# miniarduinoisp.net
KiCad netlist of a schematic drawn in EAGLE
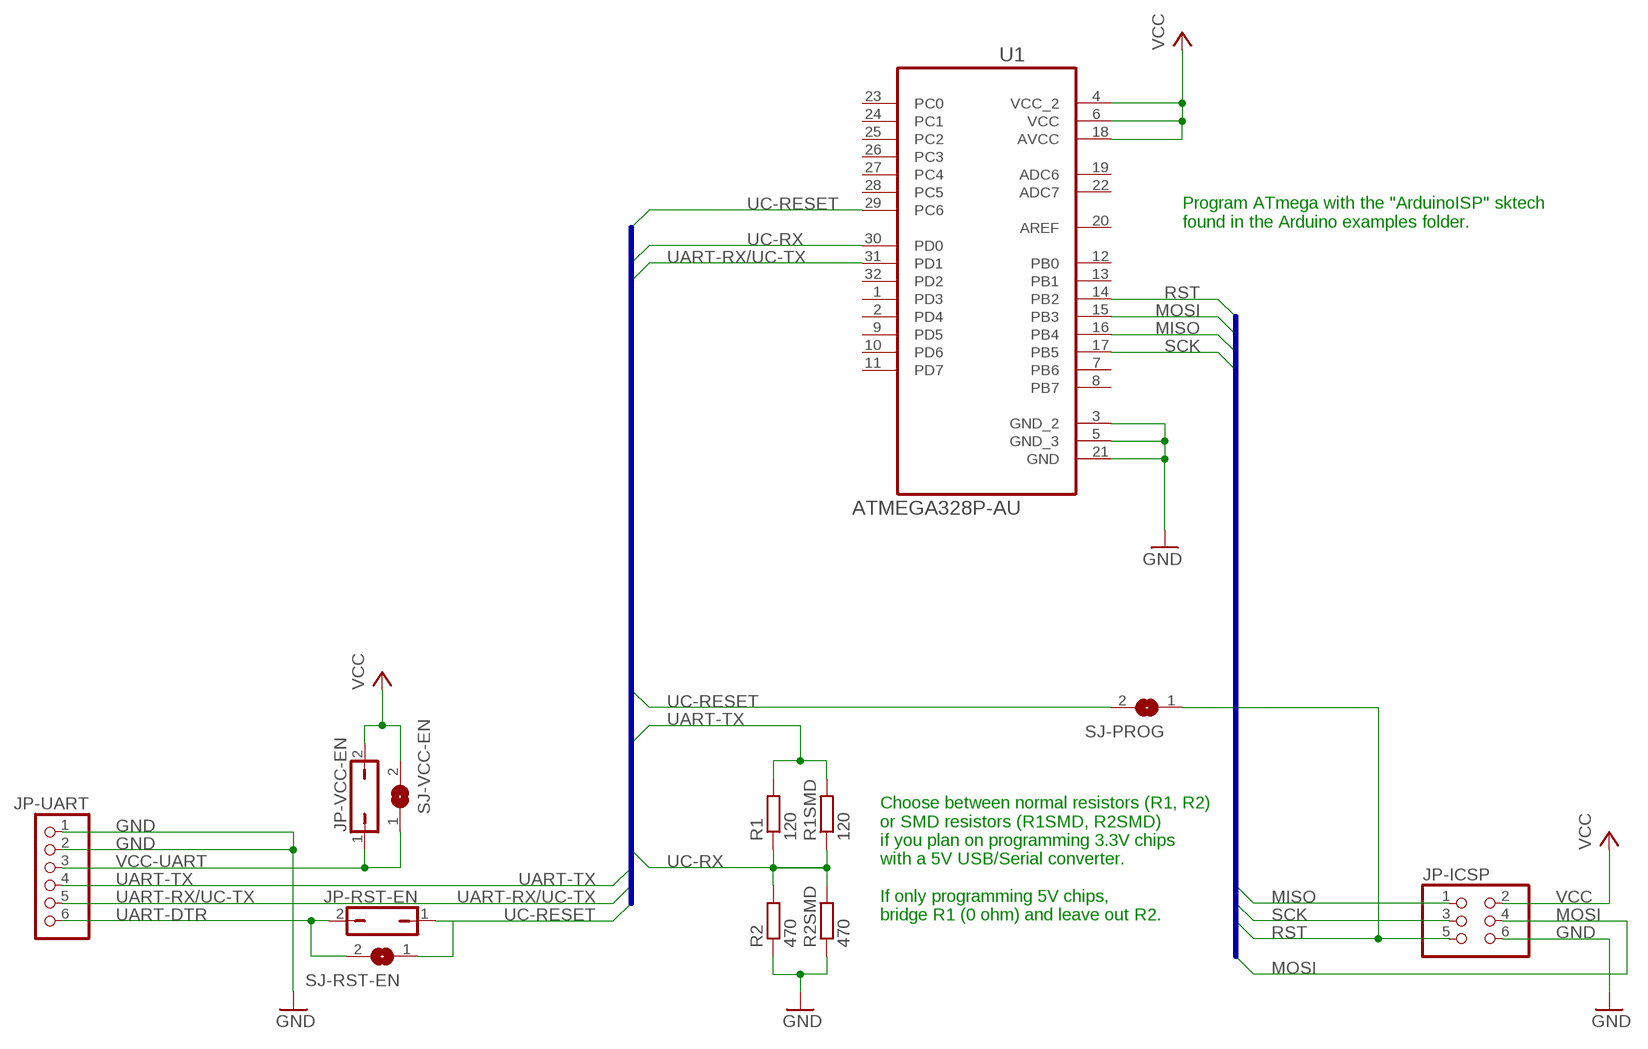
[diagram p0: schematic, sheet 1]

(export (version "E")
  (design (tool "Eeschema 10.0.6"))
  (components
    (comp (ref "JP-ICSP")
      (value "PINHD-2X3")
      (footprint "eagle-import:2X03")
      (libsource (lib "eagle-import") (part "PINHD-2X3"))
    )
    (comp (ref "JP-RST-EN")
      (value "JP1Q")
      (footprint "eagle-import:JP1")
      (libsource (lib "eagle-import") (part "JP1Q"))
    )
    (comp (ref "JP-UART")
      (value "PINHD-1X6/90")
      (footprint "eagle-import:1X06_90")
      (libsource (lib "eagle-import") (part "PINHD-1X6/90"))
    )
    (comp (ref "JP-VCC-EN")
      (value "JP1Q")
      (footprint "eagle-import:JP1")
      (libsource (lib "eagle-import") (part "JP1Q"))
    )
    (comp (ref "R1")
      (value "120")
      (footprint "eagle-import:0204_7")
      (libsource (lib "eagle-import") (part "R-EU_0204/7"))
    )
    (comp (ref "R1SMD")
      (value "120")
      (footprint "eagle-import:R0603")
      (libsource (lib "eagle-import") (part "R-EU_R0603"))
    )
    (comp (ref "R2")
      (value "470")
      (footprint "eagle-import:0204_7")
      (libsource (lib "eagle-import") (part "R-EU_0204/7"))
    )
    (comp (ref "R2SMD")
      (value "470")
      (footprint "eagle-import:R0603")
      (libsource (lib "eagle-import") (part "R-EU_R0603"))
    )
    (comp (ref "SJ-PROG")
      (value "SJ")
      (footprint "eagle-import:SJ")
      (libsource (lib "eagle-import") (part "SJ"))
    )
    (comp (ref "SJ-RST-EN")
      (value "SJ")
      (footprint "eagle-import:SJ")
      (libsource (lib "eagle-import") (part "SJ"))
    )
    (comp (ref "SJ-VCC-EN")
      (value "SJ")
      (footprint "eagle-import:SJ")
      (libsource (lib "eagle-import") (part "SJ"))
    )
    (comp (ref "U1")
      (value "ATMEGA328P-AU")
      (footprint "eagle-import:QFP80P900X900X120-32N")
      (libsource (lib "eagle-import") (part "ATMEGA328P-AU"))
    )
  )
  (nets
    (net (code "1") (name "/MISO") (class "Default")
      (node (ref "JP-ICSP") (pin "1") (pinfunction "1_1") (pintype "passive"))
      (node (ref "U1") (pin "16") (pinfunction "PB4_16") (pintype "bidirectional"))
    )
    (net (code "2") (name "/MOSI") (class "Default")
      (node (ref "JP-ICSP") (pin "4") (pinfunction "4_4") (pintype "passive"))
      (node (ref "U1") (pin "15") (pinfunction "PB3_15") (pintype "bidirectional"))
    )
    (net (code "3") (name "/RST") (class "Default")
      (node (ref "JP-ICSP") (pin "5") (pinfunction "5_5") (pintype "passive"))
      (node (ref "SJ-PROG") (pin "1") (pinfunction "1_1") (pintype "passive"))
      (node (ref "U1") (pin "14") (pinfunction "PB2_14") (pintype "bidirectional"))
    )
    (net (code "4") (name "/SCK") (class "Default")
      (node (ref "JP-ICSP") (pin "3") (pinfunction "3_3") (pintype "passive"))
      (node (ref "U1") (pin "17") (pinfunction "PB5_17") (pintype "bidirectional"))
    )
    (net (code "5") (name "/UART-DTR") (class "Default")
      (node (ref "JP-RST-EN") (pin "2") (pinfunction "2_2") (pintype "passive"))
      (node (ref "JP-UART") (pin "6") (pinfunction "6_6") (pintype "passive"))
      (node (ref "SJ-RST-EN") (pin "2") (pinfunction "2_2") (pintype "passive"))
    )
    (net (code "6") (name "/UART-RX{slash}UC-TX") (class "Default")
      (node (ref "JP-UART") (pin "5") (pinfunction "5_5") (pintype "passive"))
      (node (ref "U1") (pin "31") (pinfunction "PD1_31") (pintype "bidirectional"))
    )
    (net (code "7") (name "/UART-TX") (class "Default")
      (node (ref "JP-UART") (pin "4") (pinfunction "4_4") (pintype "passive"))
      (node (ref "R1") (pin "2") (pinfunction "2_2") (pintype "passive"))
      (node (ref "R1SMD") (pin "2") (pinfunction "2_2") (pintype "passive"))
    )
    (net (code "8") (name "/UC-RESET") (class "Default")
      (node (ref "JP-RST-EN") (pin "1") (pinfunction "1_1") (pintype "passive"))
      (node (ref "SJ-PROG") (pin "2") (pinfunction "2_2") (pintype "passive"))
      (node (ref "SJ-RST-EN") (pin "1") (pinfunction "1_1") (pintype "passive"))
      (node (ref "U1") (pin "29") (pinfunction "PC6_29") (pintype "bidirectional"))
    )
    (net (code "9") (name "/UC-RX") (class "Default")
      (node (ref "R1") (pin "1") (pinfunction "1_1") (pintype "passive"))
      (node (ref "R1SMD") (pin "1") (pinfunction "1_1") (pintype "passive"))
      (node (ref "R2") (pin "2") (pinfunction "2_2") (pintype "passive"))
      (node (ref "R2SMD") (pin "2") (pinfunction "2_2") (pintype "passive"))
      (node (ref "U1") (pin "30") (pinfunction "PD0_30") (pintype "bidirectional"))
    )
    (net (code "10") (name "/VCC-UART") (class "Default")
      (node (ref "JP-UART") (pin "3") (pinfunction "3_3") (pintype "passive"))
      (node (ref "JP-VCC-EN") (pin "1") (pinfunction "1_1") (pintype "passive"))
      (node (ref "SJ-VCC-EN") (pin "1") (pinfunction "1_1") (pintype "passive"))
    )
    (net (code "11") (name "GND") (class "Default")
      (node (ref "JP-ICSP") (pin "6") (pinfunction "6_6") (pintype "passive"))
      (node (ref "JP-UART") (pin "1") (pinfunction "1_1") (pintype "passive"))
      (node (ref "JP-UART") (pin "2") (pinfunction "2_2") (pintype "passive"))
      (node (ref "R2") (pin "1") (pinfunction "1_1") (pintype "passive"))
      (node (ref "R2SMD") (pin "1") (pinfunction "1_1") (pintype "passive"))
      (node (ref "U1") (pin "21") (pinfunction "GND_21") (pintype "passive"))
      (node (ref "U1") (pin "3") (pinfunction "GND_2_3") (pintype "passive"))
      (node (ref "U1") (pin "5") (pinfunction "GND_3_5") (pintype "passive"))
    )
    (net (code "12") (name "VCC") (class "Default")
      (node (ref "JP-ICSP") (pin "2") (pinfunction "2_2") (pintype "passive"))
      (node (ref "JP-VCC-EN") (pin "2") (pinfunction "2_2") (pintype "passive"))
      (node (ref "SJ-VCC-EN") (pin "2") (pinfunction "2_2") (pintype "passive"))
      (node (ref "U1") (pin "18") (pinfunction "AVCC_18") (pintype "power_in"))
      (node (ref "U1") (pin "4") (pinfunction "VCC_2_4") (pintype "power_in"))
      (node (ref "U1") (pin "6") (pinfunction "VCC_6") (pintype "power_in"))
    )
    (net (code "13") (name "unconnected-(U1-ADC6-Pad19)") (class "Default")
      (node (ref "U1") (pin "19") (pinfunction "ADC6_19") (pintype "input"))
    )
    (net (code "14") (name "unconnected-(U1-ADC7-Pad22)") (class "Default")
      (node (ref "U1") (pin "22") (pinfunction "ADC7_22") (pintype "input"))
    )
    (net (code "15") (name "unconnected-(U1-AREF-Pad20)") (class "Default")
      (node (ref "U1") (pin "20") (pinfunction "AREF_20") (pintype "input"))
    )
    (net (code "16") (name "unconnected-(U1-PB0-Pad12)") (class "Default")
      (node (ref "U1") (pin "12") (pinfunction "PB0_12") (pintype "bidirectional"))
    )
    (net (code "17") (name "unconnected-(U1-PB1-Pad13)") (class "Default")
      (node (ref "U1") (pin "13") (pinfunction "PB1_13") (pintype "bidirectional"))
    )
    (net (code "18") (name "unconnected-(U1-PB6-Pad7)") (class "Default")
      (node (ref "U1") (pin "7") (pinfunction "PB6_7") (pintype "bidirectional"))
    )
    (net (code "19") (name "unconnected-(U1-PB7-Pad8)") (class "Default")
      (node (ref "U1") (pin "8") (pinfunction "PB7_8") (pintype "bidirectional"))
    )
    (net (code "20") (name "unconnected-(U1-PC0-Pad23)") (class "Default")
      (node (ref "U1") (pin "23") (pinfunction "PC0_23") (pintype "bidirectional"))
    )
    (net (code "21") (name "unconnected-(U1-PC1-Pad24)") (class "Default")
      (node (ref "U1") (pin "24") (pinfunction "PC1_24") (pintype "bidirectional"))
    )
    (net (code "22") (name "unconnected-(U1-PC2-Pad25)") (class "Default")
      (node (ref "U1") (pin "25") (pinfunction "PC2_25") (pintype "bidirectional"))
    )
    (net (code "23") (name "unconnected-(U1-PC3-Pad26)") (class "Default")
      (node (ref "U1") (pin "26") (pinfunction "PC3_26") (pintype "bidirectional"))
    )
    (net (code "24") (name "unconnected-(U1-PC4-Pad27)") (class "Default")
      (node (ref "U1") (pin "27") (pinfunction "PC4_27") (pintype "bidirectional"))
    )
    (net (code "25") (name "unconnected-(U1-PC5-Pad28)") (class "Default")
      (node (ref "U1") (pin "28") (pinfunction "PC5_28") (pintype "bidirectional"))
    )
    (net (code "26") (name "unconnected-(U1-PD2-Pad32)") (class "Default")
      (node (ref "U1") (pin "32") (pinfunction "PD2_32") (pintype "bidirectional"))
    )
    (net (code "27") (name "unconnected-(U1-PD3-Pad1)") (class "Default")
      (node (ref "U1") (pin "1") (pinfunction "PD3_1") (pintype "bidirectional"))
    )
    (net (code "28") (name "unconnected-(U1-PD4-Pad2)") (class "Default")
      (node (ref "U1") (pin "2") (pinfunction "PD4_2") (pintype "bidirectional"))
    )
    (net (code "29") (name "unconnected-(U1-PD5-Pad9)") (class "Default")
      (node (ref "U1") (pin "9") (pinfunction "PD5_9") (pintype "bidirectional"))
    )
    (net (code "30") (name "unconnected-(U1-PD6-Pad10)") (class "Default")
      (node (ref "U1") (pin "10") (pinfunction "PD6_10") (pintype "bidirectional"))
    )
    (net (code "31") (name "unconnected-(U1-PD7-Pad11)") (class "Default")
      (node (ref "U1") (pin "11") (pinfunction "PD7_11") (pintype "bidirectional"))
    )
  )
)
